# mayav2_esp32.net
KiCad netlist of a schematic drawn in EAGLE
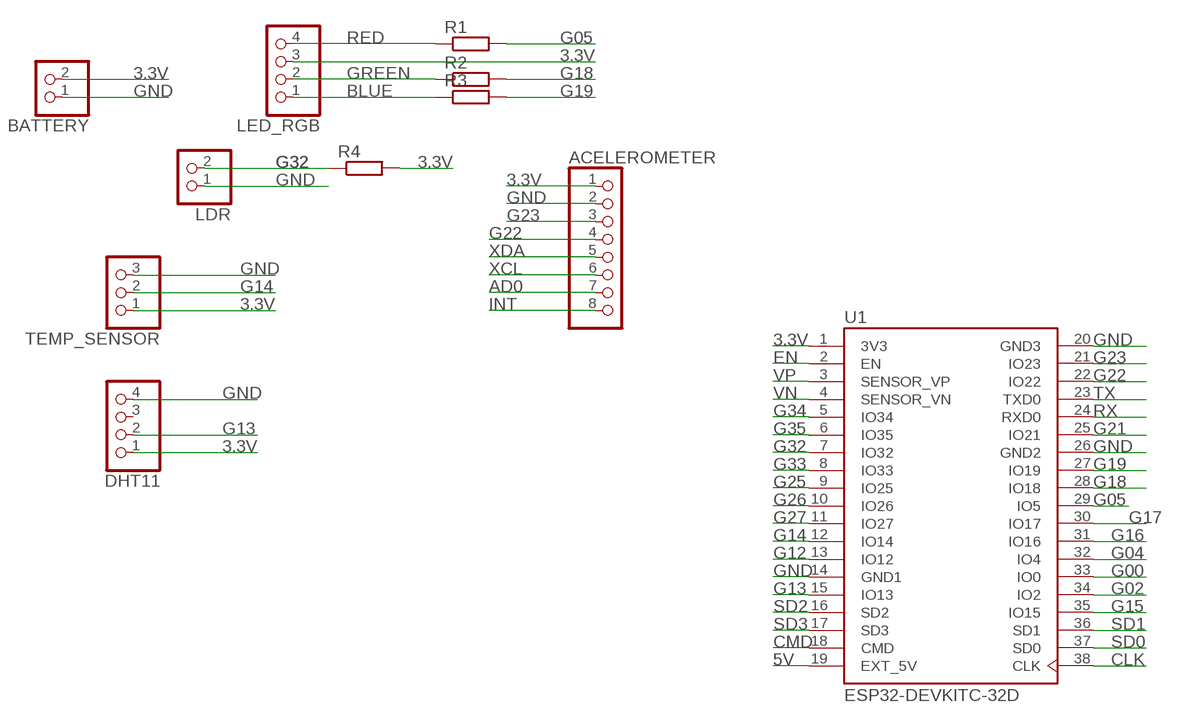
[diagram p0: schematic, sheet 1]

(export (version "E")
  (design (tool "Eeschema 10.0.6"))
  (components
    (comp (ref "ACELEROMETER")
      (value "PINHD-1X8")
      (footprint "eagle-import:1X08")
      (libsource (lib "eagle-import") (part "PINHD-1X8"))
    )
    (comp (ref "BATTERY")
      (value "PINHD-1X2")
      (footprint "eagle-import:1X02")
      (libsource (lib "eagle-import") (part "PINHD-1X2"))
    )
    (comp (ref "DHT11")
      (value "PINHD-1X4")
      (footprint "eagle-import:1X04")
      (libsource (lib "eagle-import") (part "PINHD-1X4"))
    )
    (comp (ref "LDR")
      (value "PINHD-1X2")
      (footprint "eagle-import:1X02")
      (libsource (lib "eagle-import") (part "PINHD-1X2"))
    )
    (comp (ref "LED_RGB")
      (value "PINHD-1X4")
      (footprint "eagle-import:1X04")
      (libsource (lib "eagle-import") (part "PINHD-1X4"))
    )
    (comp (ref "R1")
      (value "R-EU_0204/7")
      (footprint "eagle-import:0204_7")
      (libsource (lib "eagle-import") (part "R-EU_0204/7"))
    )
    (comp (ref "R2")
      (value "R-EU_0204/7")
      (footprint "eagle-import:0204_7")
      (libsource (lib "eagle-import") (part "R-EU_0204/7"))
    )
    (comp (ref "R3")
      (value "R-EU_0204/7")
      (footprint "eagle-import:0204_7")
      (libsource (lib "eagle-import") (part "R-EU_0204/7"))
    )
    (comp (ref "R4")
      (value "R-EU_0204/7")
      (footprint "eagle-import:0204_7")
      (libsource (lib "eagle-import") (part "R-EU_0204/7"))
    )
    (comp (ref "TEMP_SENSOR")
      (value "PINHD-1X3")
      (footprint "eagle-import:1X03")
      (libsource (lib "eagle-import") (part "PINHD-1X3"))
    )
    (comp (ref "U1")
      (value "ESP32-DEVKITC-32D")
      (footprint "eagle-import:MODULE_ESP32-DEVKITC-32D")
      (fields (field (name "MF") "Espressif Systems"))
      (libsource (lib "eagle-import") (part "ESP32-DEVKITC-32D"))
    )
  )
  (nets
    (net (code "1") (name "/3.3V") (class "Default")
      (node (ref "ACELEROMETER") (pin "1") (pinfunction "1_1") (pintype "passive"))
      (node (ref "BATTERY") (pin "2") (pinfunction "2_2") (pintype "passive"))
      (node (ref "DHT11") (pin "1") (pinfunction "1_1") (pintype "passive"))
      (node (ref "LED_RGB") (pin "3") (pinfunction "3_3") (pintype "passive"))
      (node (ref "R4") (pin "2") (pinfunction "2_2") (pintype "passive"))
      (node (ref "TEMP_SENSOR") (pin "1") (pinfunction "1_1") (pintype "passive"))
      (node (ref "U1") (pin "1") (pinfunction "3V3_1") (pintype "power_in"))
    )
    (net (code "2") (name "/5V") (class "Default")
      (node (ref "U1") (pin "19") (pinfunction "EXT_5V_19") (pintype "power_in"))
    )
    (net (code "3") (name "/AD0") (class "Default")
      (node (ref "ACELEROMETER") (pin "7") (pinfunction "7_7") (pintype "passive"))
    )
    (net (code "4") (name "/BLUE") (class "Default")
      (node (ref "LED_RGB") (pin "1") (pinfunction "1_1") (pintype "passive"))
      (node (ref "R3") (pin "1") (pinfunction "1_1") (pintype "passive"))
    )
    (net (code "5") (name "/CLK") (class "Default")
      (node (ref "U1") (pin "38") (pinfunction "CLK_38") (pintype "input"))
    )
    (net (code "6") (name "/CMD") (class "Default")
      (node (ref "U1") (pin "18") (pinfunction "CMD_18") (pintype "bidirectional"))
    )
    (net (code "7") (name "/EN") (class "Default")
      (node (ref "U1") (pin "2") (pinfunction "EN_2") (pintype "input"))
    )
    (net (code "8") (name "/G00") (class "Default")
      (node (ref "U1") (pin "33") (pinfunction "IO0_33") (pintype "bidirectional"))
    )
    (net (code "9") (name "/G02") (class "Default")
      (node (ref "U1") (pin "34") (pinfunction "IO2_34") (pintype "bidirectional"))
    )
    (net (code "10") (name "/G04") (class "Default")
      (node (ref "U1") (pin "32") (pinfunction "IO4_32") (pintype "bidirectional"))
    )
    (net (code "11") (name "/G05") (class "Default")
      (node (ref "R1") (pin "2") (pinfunction "2_2") (pintype "passive"))
      (node (ref "U1") (pin "29") (pinfunction "IO5_29") (pintype "bidirectional"))
    )
    (net (code "12") (name "/G12") (class "Default")
      (node (ref "U1") (pin "13") (pinfunction "IO12_13") (pintype "bidirectional"))
    )
    (net (code "13") (name "/G13") (class "Default")
      (node (ref "DHT11") (pin "2") (pinfunction "2_2") (pintype "passive"))
      (node (ref "U1") (pin "15") (pinfunction "IO13_15") (pintype "bidirectional"))
    )
    (net (code "14") (name "/G14") (class "Default")
      (node (ref "TEMP_SENSOR") (pin "2") (pinfunction "2_2") (pintype "passive"))
      (node (ref "U1") (pin "12") (pinfunction "IO14_12") (pintype "bidirectional"))
    )
    (net (code "15") (name "/G15") (class "Default")
      (node (ref "U1") (pin "35") (pinfunction "IO15_35") (pintype "bidirectional"))
    )
    (net (code "16") (name "/G16") (class "Default")
      (node (ref "U1") (pin "31") (pinfunction "IO16_31") (pintype "bidirectional"))
    )
    (net (code "17") (name "/G17") (class "Default")
      (node (ref "U1") (pin "30") (pinfunction "IO17_30") (pintype "bidirectional"))
    )
    (net (code "18") (name "/G18") (class "Default")
      (node (ref "R2") (pin "2") (pinfunction "2_2") (pintype "passive"))
      (node (ref "U1") (pin "28") (pinfunction "IO18_28") (pintype "bidirectional"))
    )
    (net (code "19") (name "/G19") (class "Default")
      (node (ref "R3") (pin "2") (pinfunction "2_2") (pintype "passive"))
      (node (ref "U1") (pin "27") (pinfunction "IO19_27") (pintype "bidirectional"))
    )
    (net (code "20") (name "/G21") (class "Default")
      (node (ref "U1") (pin "25") (pinfunction "IO21_25") (pintype "bidirectional"))
    )
    (net (code "21") (name "/G22") (class "Default")
      (node (ref "ACELEROMETER") (pin "4") (pinfunction "4_4") (pintype "passive"))
      (node (ref "U1") (pin "22") (pinfunction "IO22_22") (pintype "bidirectional"))
    )
    (net (code "22") (name "/G23") (class "Default")
      (node (ref "ACELEROMETER") (pin "3") (pinfunction "3_3") (pintype "passive"))
      (node (ref "U1") (pin "21") (pinfunction "IO23_21") (pintype "bidirectional"))
    )
    (net (code "23") (name "/G25") (class "Default")
      (node (ref "U1") (pin "9") (pinfunction "IO25_9") (pintype "bidirectional"))
    )
    (net (code "24") (name "/G26") (class "Default")
      (node (ref "U1") (pin "10") (pinfunction "IO26_10") (pintype "bidirectional"))
    )
    (net (code "25") (name "/G27") (class "Default")
      (node (ref "U1") (pin "11") (pinfunction "IO27_11") (pintype "bidirectional"))
    )
    (net (code "26") (name "/G32") (class "Default")
      (node (ref "LDR") (pin "2") (pinfunction "2_2") (pintype "passive"))
      (node (ref "R4") (pin "1") (pinfunction "1_1") (pintype "passive"))
      (node (ref "U1") (pin "7") (pinfunction "IO32_7") (pintype "bidirectional"))
    )
    (net (code "27") (name "/G33") (class "Default")
      (node (ref "U1") (pin "8") (pinfunction "IO33_8") (pintype "bidirectional"))
    )
    (net (code "28") (name "/G34") (class "Default")
      (node (ref "U1") (pin "5") (pinfunction "IO34_5") (pintype "bidirectional"))
    )
    (net (code "29") (name "/G35") (class "Default")
      (node (ref "U1") (pin "6") (pinfunction "IO35_6") (pintype "bidirectional"))
    )
    (net (code "30") (name "/GND") (class "Default")
      (node (ref "ACELEROMETER") (pin "2") (pinfunction "2_2") (pintype "passive"))
      (node (ref "BATTERY") (pin "1") (pinfunction "1_1") (pintype "passive"))
      (node (ref "DHT11") (pin "4") (pinfunction "4_4") (pintype "passive"))
      (node (ref "LDR") (pin "1") (pinfunction "1_1") (pintype "passive"))
      (node (ref "TEMP_SENSOR") (pin "3") (pinfunction "3_3") (pintype "passive"))
      (node (ref "U1") (pin "14") (pinfunction "GND1_14") (pintype "power_in"))
      (node (ref "U1") (pin "20") (pinfunction "GND3_20") (pintype "power_in"))
      (node (ref "U1") (pin "26") (pinfunction "GND2_26") (pintype "power_in"))
    )
    (net (code "31") (name "/GREEN") (class "Default")
      (node (ref "LED_RGB") (pin "2") (pinfunction "2_2") (pintype "passive"))
      (node (ref "R2") (pin "1") (pinfunction "1_1") (pintype "passive"))
    )
    (net (code "32") (name "/INT") (class "Default")
      (node (ref "ACELEROMETER") (pin "8") (pinfunction "8_8") (pintype "passive"))
    )
    (net (code "33") (name "/RED") (class "Default")
      (node (ref "LED_RGB") (pin "4") (pinfunction "4_4") (pintype "passive"))
      (node (ref "R1") (pin "1") (pinfunction "1_1") (pintype "passive"))
    )
    (net (code "34") (name "/RX") (class "Default")
      (node (ref "U1") (pin "24") (pinfunction "RXD0_24") (pintype "input"))
    )
    (net (code "35") (name "/SD0") (class "Default")
      (node (ref "U1") (pin "37") (pinfunction "SD0_37") (pintype "bidirectional"))
    )
    (net (code "36") (name "/SD1") (class "Default")
      (node (ref "U1") (pin "36") (pinfunction "SD1_36") (pintype "bidirectional"))
    )
    (net (code "37") (name "/SD2") (class "Default")
      (node (ref "U1") (pin "16") (pinfunction "SD2_16") (pintype "bidirectional"))
    )
    (net (code "38") (name "/SD3") (class "Default")
      (node (ref "U1") (pin "17") (pinfunction "SD3_17") (pintype "bidirectional"))
    )
    (net (code "39") (name "/TX") (class "Default")
      (node (ref "U1") (pin "23") (pinfunction "TXD0_23") (pintype "output"))
    )
    (net (code "40") (name "/VN") (class "Default")
      (node (ref "U1") (pin "4") (pinfunction "SENSOR_VN_4") (pintype "input"))
    )
    (net (code "41") (name "/VP") (class "Default")
      (node (ref "U1") (pin "3") (pinfunction "SENSOR_VP_3") (pintype "input"))
    )
    (net (code "42") (name "/XCL") (class "Default")
      (node (ref "ACELEROMETER") (pin "6") (pinfunction "6_6") (pintype "passive"))
    )
    (net (code "43") (name "/XDA") (class "Default")
      (node (ref "ACELEROMETER") (pin "5") (pinfunction "5_5") (pintype "passive"))
    )
    (net (code "44") (name "unconnected-(DHT11-Pad3)") (class "Default")
      (node (ref "DHT11") (pin "3") (pinfunction "3_3") (pintype "passive"))
    )
  )
)
